# PowerSupply.net
KiCad netlist of a schematic drawn in Altium Designer
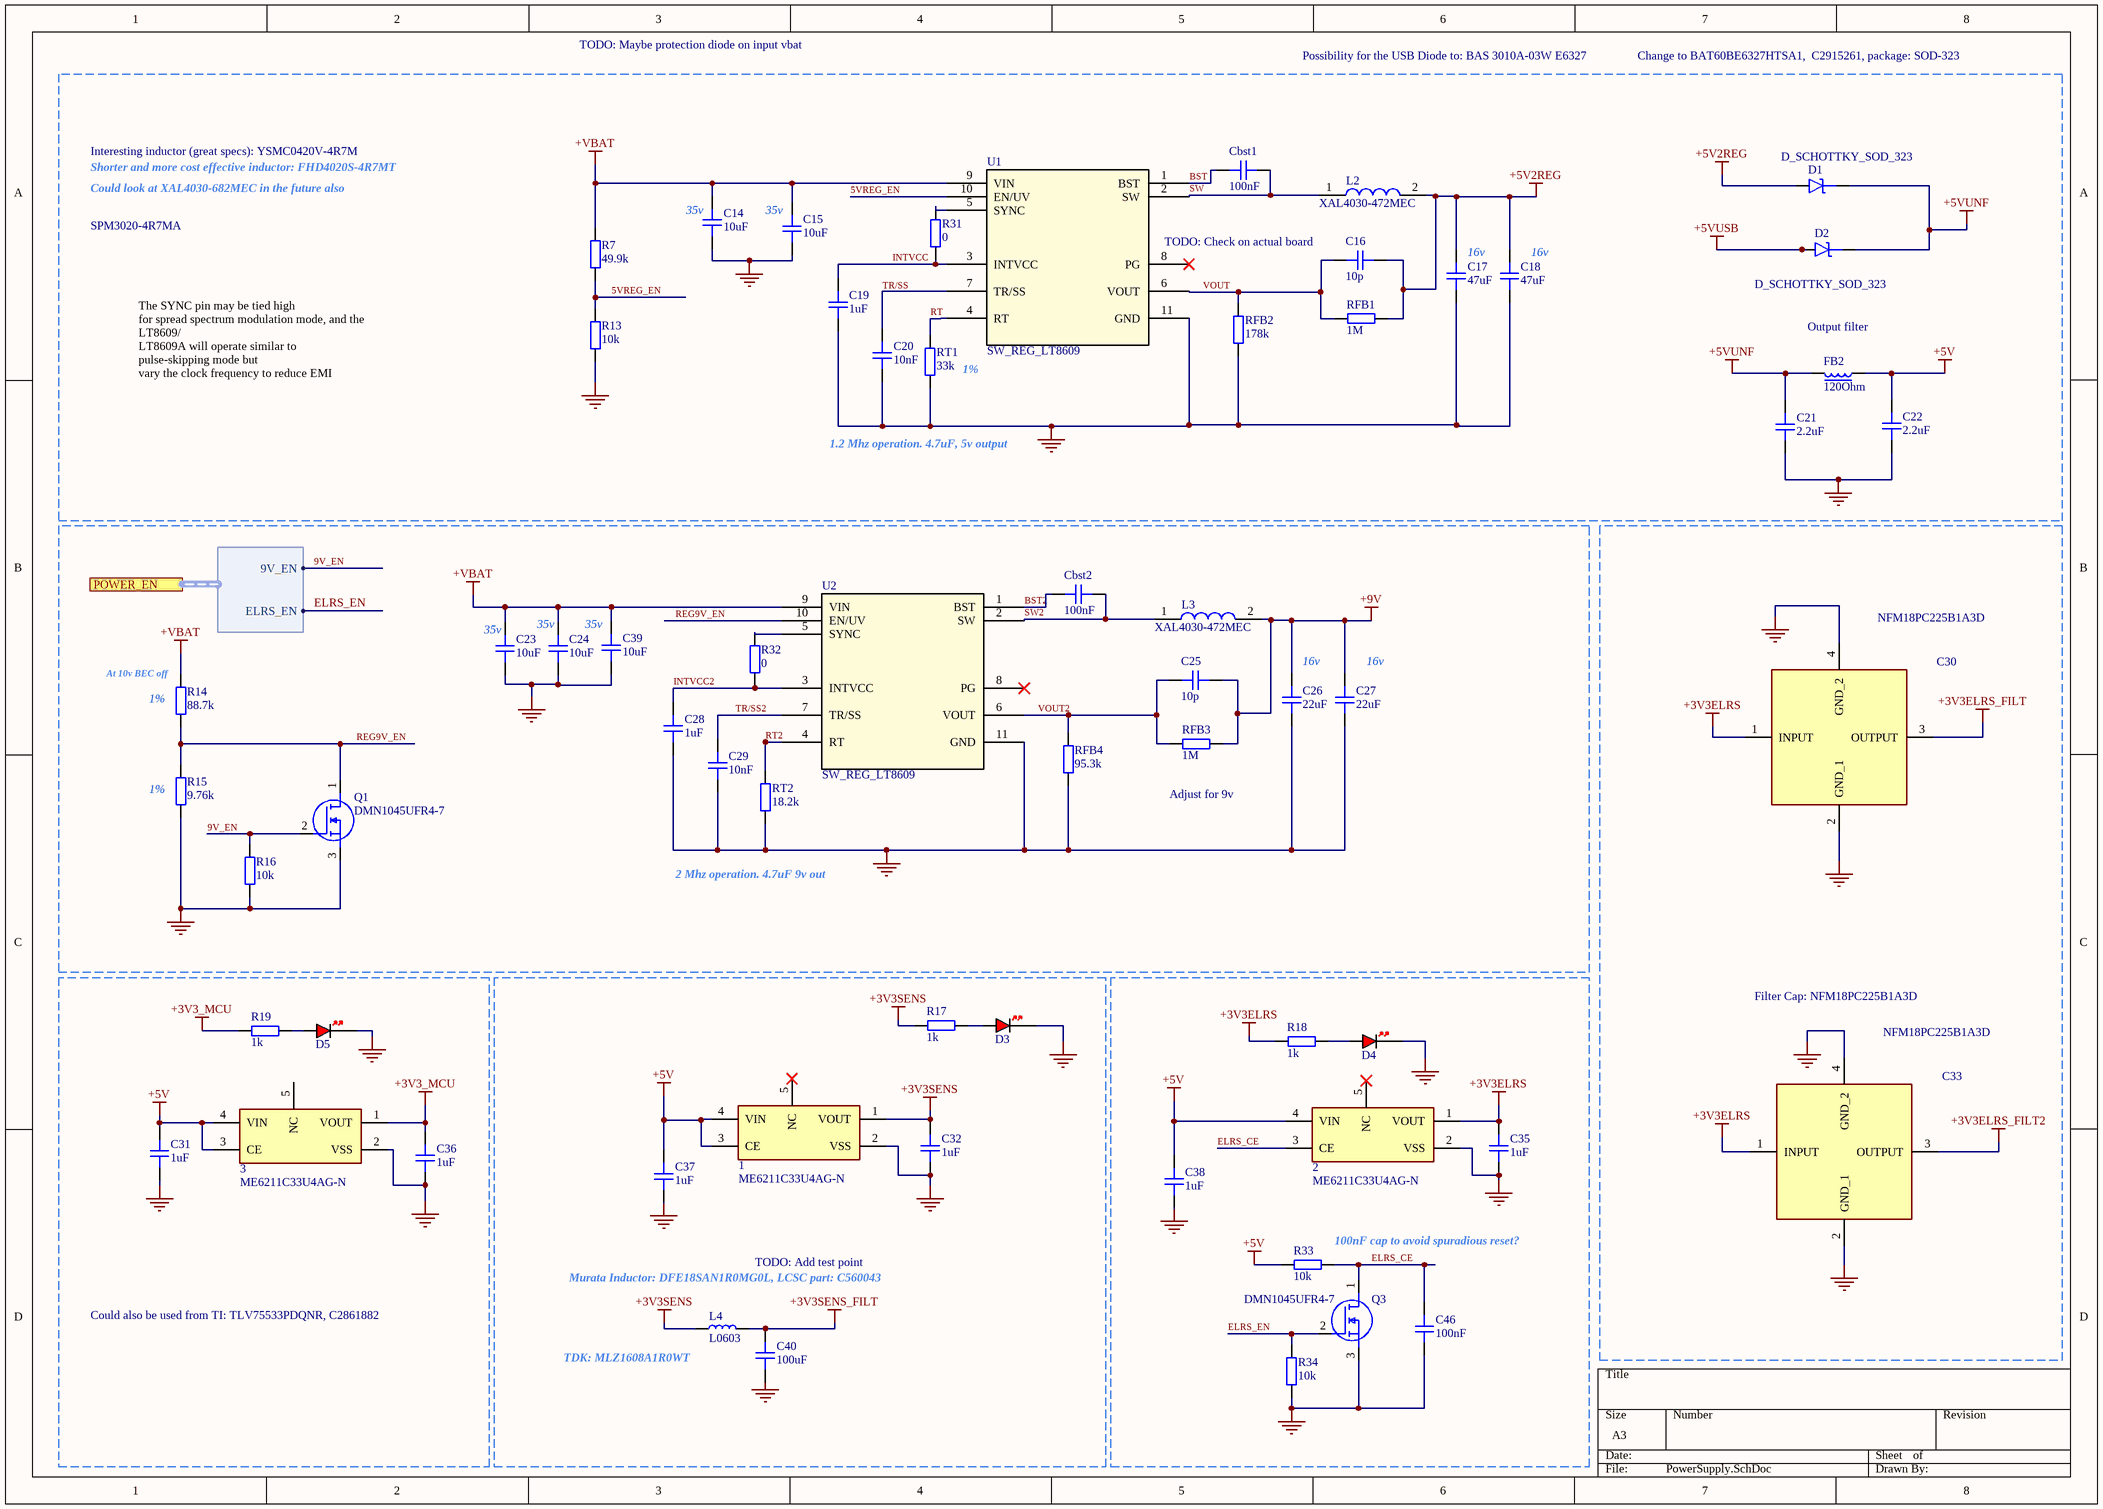
[diagram p0: PowerSupply.SchDoc]

(export (version "E")
  (design (tool "Eeschema 10.0.6"))
  (components
    (comp (ref "1")
      (value "ME6211C33U4AG-N")
      (footprint "Footprint-Lib-Singu:X2-SON-4-EP(1x1)")
      (description "Integrated Circuit")
      (fields
        (field (name "MANUFACTURER_PART_NUMBER") "ME6211C33M5G-N")
        (field (name "LCSC PART #") "C82942")
      )
      (libsource (lib "Schematic-Lib-Singu") (part "ME6211C33U4AG-N"))
    )
    (comp (ref "2")
      (value "ME6211C33U4AG-N")
      (footprint "Footprint-Lib-Singu:X2-SON-4-EP(1x1)")
      (description "Integrated Circuit")
      (fields
        (field (name "MANUFACTURER_PART_NUMBER") "ME6211C33M5G-N")
        (field (name "LCSC PART #") "C82942")
      )
      (libsource (lib "Schematic-Lib-Singu") (part "ME6211C33U4AG-N"))
    )
    (comp (ref "3")
      (value "ME6211C33U4AG-N")
      (footprint "Footprint-Lib-Singu:X2-SON-4-EP(1x1)")
      (description "Integrated Circuit")
      (fields
        (field (name "MANUFACTURER_PART_NUMBER") "ME6211C33M5G-N")
        (field (name "LCSC PART #") "C82942")
      )
      (libsource (lib "Schematic-Lib-Singu") (part "ME6211C33U4AG-N"))
    )
    (comp (ref "C14")
      (value "10uF")
      (footprint "CAP_0805")
      (description "Capacitor SMD 0805")
      (libsource (lib "Schematic-Lib-PhilsLab") (part "CAP_0805"))
    )
    (comp (ref "C15")
      (value "10uF")
      (footprint "CAP_0805")
      (description "Capacitor SMD 0805")
      (libsource (lib "Schematic-Lib-PhilsLab") (part "CAP_0805"))
    )
    (comp (ref "C16")
      (value "10p")
      (footprint "CAP_0201")
      (description "Capacitor SMD 0201")
      (libsource (lib "Schematic-Lib-PhilsLab") (part "CAP_0201"))
    )
    (comp (ref "C17")
      (value "47uF")
      (footprint "CAP_0603")
      (description "Capacitor SMD 0603")
      (libsource (lib "Schematic-Lib-PhilsLab") (part "CAP_0603"))
    )
    (comp (ref "C18")
      (value "47uF")
      (footprint "CAP_0603")
      (description "Capacitor SMD 0603")
      (libsource (lib "Schematic-Lib-PhilsLab") (part "CAP_0603"))
    )
    (comp (ref "C19")
      (value "1uF")
      (footprint "CAP_0402")
      (description "Capacitor SMD 0402")
      (libsource (lib "Schematic-Lib-PhilsLab") (part "CAP_0402"))
    )
    (comp (ref "C20")
      (value "10nF")
      (footprint "CAP_0201")
      (description "Capacitor SMD 0201")
      (libsource (lib "Schematic-Lib-PhilsLab") (part "CAP_0201"))
    )
    (comp (ref "C21")
      (value "2.2uF")
      (footprint "CAP_0402")
      (description "Capacitor SMD 0402")
      (libsource (lib "Schematic-Lib-PhilsLab") (part "CAP_0402"))
    )
    (comp (ref "C22")
      (value "2.2uF")
      (footprint "CAP_0402")
      (description "Capacitor SMD 0402")
      (libsource (lib "Schematic-Lib-PhilsLab") (part "CAP_0402"))
    )
    (comp (ref "C23")
      (value "10uF")
      (footprint "CAP_0805")
      (description "Capacitor SMD 0805")
      (libsource (lib "Schematic-Lib-PhilsLab") (part "CAP_0805"))
    )
    (comp (ref "C24")
      (value "10uF")
      (footprint "CAP_0805")
      (description "Capacitor SMD 0805")
      (libsource (lib "Schematic-Lib-PhilsLab") (part "CAP_0805"))
    )
    (comp (ref "C25")
      (value "10p")
      (footprint "CAP_0201")
      (description "Capacitor SMD 0201")
      (libsource (lib "Schematic-Lib-PhilsLab") (part "CAP_0201"))
    )
    (comp (ref "C26")
      (value "22uF")
      (footprint "CAP_0603")
      (description "Capacitor SMD 0603")
      (libsource (lib "Schematic-Lib-PhilsLab") (part "CAP_0603"))
    )
    (comp (ref "C27")
      (value "22uF")
      (footprint "CAP_0603")
      (description "Capacitor SMD 0603")
      (libsource (lib "Schematic-Lib-PhilsLab") (part "CAP_0603"))
    )
    (comp (ref "C28")
      (value "1uF")
      (footprint "CAP_0402")
      (description "Capacitor SMD 0402")
      (libsource (lib "Schematic-Lib-PhilsLab") (part "CAP_0402"))
    )
    (comp (ref "C29")
      (value "10nF")
      (footprint "CAP_0201")
      (description "Capacitor SMD 0201")
      (libsource (lib "Schematic-Lib-PhilsLab") (part "CAP_0201"))
    )
    (comp (ref "C30")
      (value "NFM18PC225B1A3D")
      (footprint "SamacSys:NFM18PC225B1A3D")
      (description "Capacitor")
      (fields (field (name "MOUSER PART NUMBER") "81-NFM18PC225B1A3D"))
      (libsource (lib "*") (part "NFM18PC225B1A3D"))
    )
    (comp (ref "C31")
      (value "1uF")
      (footprint "CAP_0402")
      (description "Capacitor SMD 0402")
      (libsource (lib "Schematic-Lib-PhilsLab") (part "CAP_0402"))
    )
    (comp (ref "C32")
      (value "1uF")
      (footprint "CAP_0402")
      (description "Capacitor SMD 0402")
      (libsource (lib "Schematic-Lib-PhilsLab") (part "CAP_0402"))
    )
    (comp (ref "C33")
      (value "NFM18PC225B1A3D")
      (footprint "SamacSys:NFM18PC225B1A3D")
      (description "Capacitor")
      (fields (field (name "MOUSER PART NUMBER") "81-NFM18PC225B1A3D"))
      (libsource (lib "*") (part "NFM18PC225B1A3D"))
    )
    (comp (ref "C35")
      (value "1uF")
      (footprint "CAP_0402")
      (description "Capacitor SMD 0402")
      (libsource (lib "Schematic-Lib-PhilsLab") (part "CAP_0402"))
    )
    (comp (ref "C36")
      (value "1uF")
      (footprint "CAP_0402")
      (description "Capacitor SMD 0402")
      (libsource (lib "Schematic-Lib-PhilsLab") (part "CAP_0402"))
    )
    (comp (ref "C37")
      (value "1uF")
      (footprint "CAP_0402")
      (description "Capacitor SMD 0402")
      (libsource (lib "Schematic-Lib-PhilsLab") (part "CAP_0402"))
    )
    (comp (ref "C38")
      (value "1uF")
      (footprint "CAP_0402")
      (description "Capacitor SMD 0402")
      (libsource (lib "Schematic-Lib-PhilsLab") (part "CAP_0402"))
    )
    (comp (ref "C39")
      (value "10uF")
      (footprint "CAP_0603")
      (description "Capacitor SMD 0603")
      (libsource (lib "Schematic-Lib-PhilsLab") (part "CAP_0603"))
    )
    (comp (ref "C40")
      (value "100uF")
      (footprint "CAP_0805")
      (description "Capacitor SMD 0805")
      (libsource (lib "Schematic-Lib-PhilsLab") (part "CAP_0805"))
    )
    (comp (ref "C46")
      (value "100nF")
      (footprint "CAP_0201")
      (description "Capacitor SMD 0201")
      (libsource (lib "Schematic-Lib-PhilsLab") (part "CAP_0201"))
    )
    (comp (ref "Cbst1")
      (value "100nF")
      (footprint "CAP_0201")
      (description "Capacitor SMD 0201")
      (libsource (lib "Schematic-Lib-PhilsLab") (part "CAP_0201"))
    )
    (comp (ref "Cbst2")
      (value "100nF")
      (footprint "CAP_0201")
      (description "Capacitor SMD 0201")
      (libsource (lib "Schematic-Lib-PhilsLab") (part "CAP_0201"))
    )
    (comp (ref "D1")
      (value "D_SCHOTTKY_SOD_323")
      (footprint "SOD-323")
      (description "Diode Schottky SMD SOD-323")
      (libsource (lib "Schematic-Lib-PhilsLab") (part "D_SCHOTTKY_SOD_323"))
    )
    (comp (ref "D2")
      (value "D_SCHOTTKY_SOD_323")
      (footprint "SOD-323")
      (description "Diode Schottky SMD SOD-323")
      (libsource (lib "Schematic-Lib-PhilsLab") (part "D_SCHOTTKY_SOD_323"))
    )
    (comp (ref "D3")
      (value "RED")
      (footprint "LED_0402_RED")
      (description "LED 0402 RED SMD")
      (libsource (lib "Schematic-Lib-PhilsLab") (part "LED_0402_RED"))
    )
    (comp (ref "D4")
      (value "RED")
      (footprint "LED_0402_RED")
      (description "LED 0402 RED SMD")
      (libsource (lib "Schematic-Lib-PhilsLab") (part "LED_0402_RED"))
    )
    (comp (ref "D5")
      (value "RED")
      (footprint "LED_0402_RED")
      (description "LED 0402 RED SMD")
      (libsource (lib "Schematic-Lib-PhilsLab") (part "LED_0402_RED"))
    )
    (comp (ref "FB2")
      (value "120Ohm")
      (footprint "FB_0603")
      (description "Ferrite Bead SMD 0603")
      (libsource (lib "Schematic-Lib-PhilsLab") (part "FB_0603"))
    )
    (comp (ref "L2")
      (value "XAL4030-472MEC")
      (footprint "Footprint-Lib-Singu:IND-SMD_L4.0-W4.0")
      (description "Inductor")
      (fields (field (name "MOUSER PART NUMBER") "994-XAL4030-472MEC"))
      (libsource (lib "Schematic-Lib-Singu") (part "XAL4030-472MEC"))
    )
    (comp (ref "L3")
      (value "XAL4030-472MEC")
      (footprint "Footprint-Lib-Singu:IND-SMD_L4.0-W4.0")
      (description "Inductor")
      (fields (field (name "MOUSER PART NUMBER") "994-XAL4030-472MEC"))
      (libsource (lib "Schematic-Lib-Singu") (part "XAL4030-472MEC"))
    )
    (comp (ref "L4")
      (value "L0603")
      (footprint "IND_0603")
      (description "Inductor SMD 0603")
      (libsource (lib "Schematic-Lib-PhilsLab") (part "IND_0603"))
    )
    (comp (ref "Q1")
      (value "DMN1045UFR4-7")
      (footprint "Footprint-Lib-Singu:DMP1200UFR47")
      (description "MOSFET (N-Channel)")
      (fields (field (name "MOUSER PART NUMBER") "621-DMN1045UFR4-7"))
      (libsource (lib "Schematic-Lib-Singu") (part "DMN1045UFR4-7"))
    )
    (comp (ref "Q3")
      (value "DMN1045UFR4-7")
      (footprint "Footprint-Lib-Singu:DMP1200UFR47")
      (description "MOSFET (N-Channel)")
      (fields (field (name "MOUSER PART NUMBER") "621-DMN1045UFR4-7"))
      (libsource (lib "Schematic-Lib-Singu") (part "DMN1045UFR4-7"))
    )
    (comp (ref "R7")
      (value "49.9k")
      (footprint "RES_0402")
      (description "Resistor SMD 0402")
      (libsource (lib "Schematic-Lib-PhilsLab") (part "RES_0402"))
    )
    (comp (ref "R13")
      (value "10k")
      (footprint "RES_0201")
      (description "Resistor SMD 0201")
      (libsource (lib "Schematic-Lib-PhilsLab") (part "RES_0201"))
    )
    (comp (ref "R14")
      (value "88.7k")
      (footprint "RES_0402")
      (description "Resistor SMD 0402")
      (libsource (lib "Schematic-Lib-PhilsLab") (part "RES_0402"))
    )
    (comp (ref "R15")
      (value "9.76k")
      (footprint "RES_0201")
      (description "Resistor SMD 0201")
      (libsource (lib "Schematic-Lib-PhilsLab") (part "RES_0201"))
    )
    (comp (ref "R16")
      (value "10k")
      (footprint "RES_0201")
      (description "Resistor SMD 0201")
      (libsource (lib "Schematic-Lib-PhilsLab") (part "RES_0201"))
    )
    (comp (ref "R17")
      (value "1k")
      (footprint "RES_0201")
      (description "Resistor SMD 0201")
      (libsource (lib "Schematic-Lib-PhilsLab") (part "RES_0201"))
    )
    (comp (ref "R18")
      (value "1k")
      (footprint "RES_0201")
      (description "Resistor SMD 0201")
      (libsource (lib "Schematic-Lib-PhilsLab") (part "RES_0201"))
    )
    (comp (ref "R19")
      (value "1k")
      (footprint "RES_0201")
      (description "Resistor SMD 0201")
      (libsource (lib "Schematic-Lib-PhilsLab") (part "RES_0201"))
    )
    (comp (ref "R31")
      (value "0")
      (footprint "RES_0201")
      (description "Resistor SMD 0201")
      (libsource (lib "Schematic-Lib-PhilsLab") (part "RES_0201"))
    )
    (comp (ref "R32")
      (value "0")
      (footprint "RES_0201")
      (description "Resistor SMD 0201")
      (libsource (lib "Schematic-Lib-PhilsLab") (part "RES_0201"))
    )
    (comp (ref "R33")
      (value "10k")
      (footprint "RES_0201")
      (description "Resistor SMD 0201")
      (libsource (lib "Schematic-Lib-PhilsLab") (part "RES_0201"))
    )
    (comp (ref "R34")
      (value "10k")
      (footprint "RES_0201")
      (description "Resistor SMD 0201")
      (libsource (lib "Schematic-Lib-PhilsLab") (part "RES_0201"))
    )
    (comp (ref "RFB1")
      (value "1M")
      (footprint "RES_0201")
      (description "Resistor SMD 0201")
      (libsource (lib "Schematic-Lib-PhilsLab") (part "RES_0201"))
    )
    (comp (ref "RFB2")
      (value "178k")
      (footprint "RES_0201")
      (description "Resistor SMD 0201")
      (libsource (lib "Schematic-Lib-PhilsLab") (part "RES_0201"))
    )
    (comp (ref "RFB3")
      (value "1M")
      (footprint "RES_0201")
      (description "Resistor SMD 0201")
      (libsource (lib "Schematic-Lib-PhilsLab") (part "RES_0201"))
    )
    (comp (ref "RFB4")
      (value "95.3k")
      (footprint "RES_0201")
      (description "Resistor SMD 0201")
      (libsource (lib "Schematic-Lib-PhilsLab") (part "RES_0201"))
    )
    (comp (ref "RT1")
      (value "33k")
      (footprint "RES_0201")
      (description "Resistor SMD 0201")
      (libsource (lib "Schematic-Lib-PhilsLab") (part "RES_0201"))
    )
    (comp (ref "RT2")
      (value "18.2k")
      (footprint "RES_0201")
      (description "Resistor SMD 0201")
      (libsource (lib "Schematic-Lib-PhilsLab") (part "RES_0201"))
    )
    (comp (ref "U1")
      (value "SW_REG_LT8609")
      (footprint "SW_REG_LT8609")
      (fields (field (name "MFR.PART") "LT8609AJDDM#WTRPBF") (field (name "LCSC PART #") "C5122347"))
      (libsource (lib "Schematic-Lib-Singu") (part "SW_REG_LT8609"))
    )
    (comp (ref "U2")
      (value "SW_REG_LT8609")
      (footprint "SW_REG_LT8609")
      (fields (field (name "MFR.PART") "LT8609AJDDM#WTRPBF") (field (name "LCSC PART #") "C5122347"))
      (libsource (lib "Schematic-Lib-Singu") (part "SW_REG_LT8609"))
    )
  )
  (nets
    (net (code "2") (name "+3V3ELRS") (class "Default")
      (node (ref "2") (pin "1") (pinfunction "VOUT_1") (pintype "passive"))
      (node (ref "C30") (pin "1") (pinfunction "INPUT_1") (pintype "passive"))
      (node (ref "C33") (pin "1") (pinfunction "INPUT_1") (pintype "passive"))
      (node (ref "C35") (pin "2") (pinfunction "2_2") (pintype "passive"))
      (node (ref "R18") (pin "1") (pinfunction "1_1") (pintype "passive"))
    )
    (net (code "3") (name "+3V3ELRS_FILT") (class "Default")
      (node (ref "C30") (pin "3") (pinfunction "OUTPUT_3") (pintype "passive"))
    )
    (net (code "4") (name "+3V3ELRS_FILT2") (class "Default")
      (node (ref "C33") (pin "3") (pinfunction "OUTPUT_3") (pintype "passive"))
    )
    (net (code "5") (name "+3V3SENS") (class "Default")
      (node (ref "1") (pin "1") (pinfunction "VOUT_1") (pintype "passive"))
      (node (ref "C32") (pin "2") (pinfunction "2_2") (pintype "passive"))
      (node (ref "L4") (pin "1") (pinfunction "1_1") (pintype "passive"))
      (node (ref "R17") (pin "1") (pinfunction "1_1") (pintype "passive"))
    )
    (net (code "6") (name "+3V3SENS_FILT") (class "Default")
      (node (ref "C40") (pin "2") (pinfunction "2_2") (pintype "passive"))
      (node (ref "L4") (pin "2") (pinfunction "2_2") (pintype "passive"))
    )
    (net (code "7") (name "+3V3_MCU") (class "Default")
      (node (ref "3") (pin "1") (pinfunction "VOUT_1") (pintype "passive"))
      (node (ref "C36") (pin "2") (pinfunction "2_2") (pintype "passive"))
      (node (ref "R19") (pin "1") (pinfunction "1_1") (pintype "passive"))
    )
    (net (code "8") (name "+5V") (class "Default")
      (node (ref "1") (pin "3") (pinfunction "CE_3") (pintype "passive"))
      (node (ref "1") (pin "4") (pinfunction "VIN_4") (pintype "passive"))
      (node (ref "2") (pin "4") (pinfunction "VIN_4") (pintype "passive"))
      (node (ref "3") (pin "3") (pinfunction "CE_3") (pintype "passive"))
      (node (ref "3") (pin "4") (pinfunction "VIN_4") (pintype "passive"))
      (node (ref "C22") (pin "2") (pinfunction "2_2") (pintype "passive"))
      (node (ref "C31") (pin "2") (pinfunction "2_2") (pintype "passive"))
      (node (ref "C37") (pin "2") (pinfunction "2_2") (pintype "passive"))
      (node (ref "C38") (pin "2") (pinfunction "2_2") (pintype "passive"))
      (node (ref "FB2") (pin "1") (pinfunction "1_1") (pintype "passive"))
      (node (ref "R33") (pin "2") (pinfunction "2_2") (pintype "passive"))
    )
    (net (code "9") (name "+5V2REG") (class "Default")
      (node (ref "C16") (pin "2") (pinfunction "2_2") (pintype "passive"))
      (node (ref "C17") (pin "1") (pinfunction "1_1") (pintype "passive"))
      (node (ref "C18") (pin "1") (pinfunction "1_1") (pintype "passive"))
      (node (ref "D1") (pin "A") (pinfunction "A_A") (pintype "passive"))
      (node (ref "L2") (pin "2") (pinfunction "2_2") (pintype "passive"))
      (node (ref "RFB1") (pin "1") (pinfunction "1_1") (pintype "passive"))
    )
    (net (code "10") (name "+5VUNF") (class "Default")
      (node (ref "C21") (pin "2") (pinfunction "2_2") (pintype "passive"))
      (node (ref "D1") (pin "K") (pinfunction "K_K") (pintype "passive"))
      (node (ref "D2") (pin "K") (pinfunction "K_K") (pintype "passive"))
      (node (ref "FB2") (pin "2") (pinfunction "2_2") (pintype "passive"))
    )
    (net (code "11") (name "+5VUSB") (class "Default")
      (node (ref "D2") (pin "A") (pinfunction "A_A") (pintype "passive"))
    )
    (net (code "12") (name "+9V") (class "Default")
      (node (ref "C25") (pin "2") (pinfunction "2_2") (pintype "passive"))
      (node (ref "C26") (pin "1") (pinfunction "1_1") (pintype "passive"))
      (node (ref "C27") (pin "1") (pinfunction "1_1") (pintype "passive"))
      (node (ref "L3") (pin "2") (pinfunction "2_2") (pintype "passive"))
      (node (ref "RFB3") (pin "1") (pinfunction "1_1") (pintype "passive"))
    )
    (net (code "13") (name "+VBAT") (class "Default")
      (node (ref "C14") (pin "2") (pinfunction "2_2") (pintype "passive"))
      (node (ref "C15") (pin "2") (pinfunction "2_2") (pintype "passive"))
      (node (ref "C23") (pin "2") (pinfunction "2_2") (pintype "passive"))
      (node (ref "C24") (pin "2") (pinfunction "2_2") (pintype "passive"))
      (node (ref "C39") (pin "2") (pinfunction "2_2") (pintype "passive"))
      (node (ref "R14") (pin "2") (pinfunction "2_2") (pintype "passive"))
      (node (ref "R7") (pin "2") (pinfunction "2_2") (pintype "passive"))
      (node (ref "U1") (pin "9") (pinfunction "VIN_9") (pintype "passive"))
      (node (ref "U2") (pin "9") (pinfunction "VIN_9") (pintype "passive"))
    )
    (net (code "14") (name "/5VREG_EN") (class "Default")
      (node (ref "R13") (pin "2") (pinfunction "2_2") (pintype "passive"))
      (node (ref "R7") (pin "1") (pinfunction "1_1") (pintype "passive"))
      (node (ref "U1") (pin "10") (pinfunction "EN/UV_10") (pintype "passive"))
    )
    (net (code "15") (name "/9V_EN") (class "Default")
      (node (ref "Q1") (pin "2") (pinfunction "G_2") (pintype "passive"))
      (node (ref "R16") (pin "2") (pinfunction "2_2") (pintype "passive"))
    )
    (net (code "16") (name "/BST") (class "Default")
      (node (ref "Cbst1") (pin "1") (pinfunction "1_1") (pintype "passive"))
      (node (ref "U1") (pin "1") (pinfunction "BST_1") (pintype "passive"))
    )
    (net (code "17") (name "/BST2") (class "Default")
      (node (ref "Cbst2") (pin "1") (pinfunction "1_1") (pintype "passive"))
      (node (ref "U2") (pin "1") (pinfunction "BST_1") (pintype "passive"))
    )
    (net (code "18") (name "/ELRS_CE") (class "Default")
      (node (ref "2") (pin "3") (pinfunction "CE_3") (pintype "passive"))
      (node (ref "C46") (pin "2") (pinfunction "2_2") (pintype "passive"))
      (node (ref "Q3") (pin "1") (pinfunction "D_1") (pintype "passive"))
      (node (ref "R33") (pin "1") (pinfunction "1_1") (pintype "passive"))
    )
    (net (code "19") (name "/ELRS_EN") (class "Default")
      (node (ref "Q3") (pin "2") (pinfunction "G_2") (pintype "passive"))
      (node (ref "R34") (pin "2") (pinfunction "2_2") (pintype "passive"))
    )
    (net (code "20") (name "/INTVCC") (class "Default")
      (node (ref "C19") (pin "2") (pinfunction "2_2") (pintype "passive"))
      (node (ref "R31") (pin "1") (pinfunction "1_1") (pintype "passive"))
      (node (ref "U1") (pin "3") (pinfunction "INTVCC_3") (pintype "passive"))
    )
    (net (code "21") (name "/INTVCC2") (class "Default")
      (node (ref "C28") (pin "2") (pinfunction "2_2") (pintype "passive"))
      (node (ref "R32") (pin "1") (pinfunction "1_1") (pintype "passive"))
      (node (ref "U2") (pin "3") (pinfunction "INTVCC_3") (pintype "passive"))
    )
    (net (code "22") (name "/REG9V_EN") (class "Default")
      (node (ref "Q1") (pin "1") (pinfunction "D_1") (pintype "passive"))
      (node (ref "R14") (pin "1") (pinfunction "1_1") (pintype "passive"))
      (node (ref "R15") (pin "2") (pinfunction "2_2") (pintype "passive"))
      (node (ref "U2") (pin "10") (pinfunction "EN/UV_10") (pintype "passive"))
    )
    (net (code "23") (name "/RT") (class "Default")
      (node (ref "RT1") (pin "2") (pinfunction "2_2") (pintype "passive"))
      (node (ref "U1") (pin "4") (pinfunction "RT_4") (pintype "passive"))
    )
    (net (code "24") (name "/RT2") (class "Default")
      (node (ref "RT2") (pin "1") (pinfunction "1_1") (pintype "passive"))
      (node (ref "U2") (pin "4") (pinfunction "RT_4") (pintype "passive"))
    )
    (net (code "25") (name "/SW") (class "Default")
      (node (ref "Cbst1") (pin "2") (pinfunction "2_2") (pintype "passive"))
      (node (ref "L2") (pin "1") (pinfunction "1_1") (pintype "passive"))
      (node (ref "U1") (pin "2") (pinfunction "SW_2") (pintype "passive"))
    )
    (net (code "26") (name "/SW2") (class "Default")
      (node (ref "Cbst2") (pin "2") (pinfunction "2_2") (pintype "passive"))
      (node (ref "L3") (pin "1") (pinfunction "1_1") (pintype "passive"))
      (node (ref "U2") (pin "2") (pinfunction "SW_2") (pintype "passive"))
    )
    (net (code "27") (name "/TR{slash}SS") (class "Default")
      (node (ref "C20") (pin "2") (pinfunction "2_2") (pintype "passive"))
      (node (ref "U1") (pin "7") (pinfunction "TR/SS_7") (pintype "passive"))
    )
    (net (code "28") (name "/TR{slash}SS2") (class "Default")
      (node (ref "C29") (pin "2") (pinfunction "2_2") (pintype "passive"))
      (node (ref "U2") (pin "7") (pinfunction "TR/SS_7") (pintype "passive"))
    )
    (net (code "29") (name "/VOUT") (class "Default")
      (node (ref "C16") (pin "1") (pinfunction "1_1") (pintype "passive"))
      (node (ref "RFB1") (pin "2") (pinfunction "2_2") (pintype "passive"))
      (node (ref "RFB2") (pin "2") (pinfunction "2_2") (pintype "passive"))
      (node (ref "U1") (pin "6") (pinfunction "VOUT_6") (pintype "passive"))
    )
    (net (code "30") (name "/VOUT2") (class "Default")
      (node (ref "C25") (pin "1") (pinfunction "1_1") (pintype "passive"))
      (node (ref "RFB3") (pin "2") (pinfunction "2_2") (pintype "passive"))
      (node (ref "RFB4") (pin "2") (pinfunction "2_2") (pintype "passive"))
      (node (ref "U2") (pin "6") (pinfunction "VOUT_6") (pintype "passive"))
    )
    (net (code "32") (name "GND") (class "Default")
      (node (ref "1") (pin "2") (pinfunction "VSS_2") (pintype "passive"))
      (node (ref "2") (pin "2") (pinfunction "VSS_2") (pintype "passive"))
      (node (ref "3") (pin "2") (pinfunction "VSS_2") (pintype "passive"))
      (node (ref "C14") (pin "1") (pinfunction "1_1") (pintype "passive"))
      (node (ref "C15") (pin "1") (pinfunction "1_1") (pintype "passive"))
      (node (ref "C17") (pin "2") (pinfunction "2_2") (pintype "passive"))
      (node (ref "C18") (pin "2") (pinfunction "2_2") (pintype "passive"))
      (node (ref "C19") (pin "1") (pinfunction "1_1") (pintype "passive"))
      (node (ref "C20") (pin "1") (pinfunction "1_1") (pintype "passive"))
      (node (ref "C21") (pin "1") (pinfunction "1_1") (pintype "passive"))
      (node (ref "C22") (pin "1") (pinfunction "1_1") (pintype "passive"))
      (node (ref "C23") (pin "1") (pinfunction "1_1") (pintype "passive"))
      (node (ref "C24") (pin "1") (pinfunction "1_1") (pintype "passive"))
      (node (ref "C26") (pin "2") (pinfunction "2_2") (pintype "passive"))
      (node (ref "C27") (pin "2") (pinfunction "2_2") (pintype "passive"))
      (node (ref "C28") (pin "1") (pinfunction "1_1") (pintype "passive"))
      (node (ref "C29") (pin "1") (pinfunction "1_1") (pintype "passive"))
      (node (ref "C30") (pin "2") (pinfunction "GND_1_2") (pintype "passive"))
      (node (ref "C30") (pin "4") (pinfunction "GND_2_4") (pintype "passive"))
      (node (ref "C31") (pin "1") (pinfunction "1_1") (pintype "passive"))
      (node (ref "C32") (pin "1") (pinfunction "1_1") (pintype "passive"))
      (node (ref "C33") (pin "2") (pinfunction "GND_1_2") (pintype "passive"))
      (node (ref "C33") (pin "4") (pinfunction "GND_2_4") (pintype "passive"))
      (node (ref "C35") (pin "1") (pinfunction "1_1") (pintype "passive"))
      (node (ref "C36") (pin "1") (pinfunction "1_1") (pintype "passive"))
      (node (ref "C37") (pin "1") (pinfunction "1_1") (pintype "passive"))
      (node (ref "C38") (pin "1") (pinfunction "1_1") (pintype "passive"))
      (node (ref "C39") (pin "1") (pinfunction "1_1") (pintype "passive"))
      (node (ref "C40") (pin "1") (pinfunction "1_1") (pintype "passive"))
      (node (ref "C46") (pin "1") (pinfunction "1_1") (pintype "passive"))
      (node (ref "D3") (pin "K") (pinfunction "K_K") (pintype "passive"))
      (node (ref "D4") (pin "K") (pinfunction "K_K") (pintype "passive"))
      (node (ref "D5") (pin "K") (pinfunction "K_K") (pintype "passive"))
      (node (ref "Q1") (pin "3") (pinfunction "S_3") (pintype "passive"))
      (node (ref "Q3") (pin "3") (pinfunction "S_3") (pintype "passive"))
      (node (ref "R13") (pin "1") (pinfunction "1_1") (pintype "passive"))
      (node (ref "R15") (pin "1") (pinfunction "1_1") (pintype "passive"))
      (node (ref "R16") (pin "1") (pinfunction "1_1") (pintype "passive"))
      (node (ref "R34") (pin "1") (pinfunction "1_1") (pintype "passive"))
      (node (ref "RFB2") (pin "1") (pinfunction "1_1") (pintype "passive"))
      (node (ref "RFB4") (pin "1") (pinfunction "1_1") (pintype "passive"))
      (node (ref "RT1") (pin "1") (pinfunction "1_1") (pintype "passive"))
      (node (ref "RT2") (pin "2") (pinfunction "2_2") (pintype "passive"))
      (node (ref "U1") (pin "11") (pinfunction "GND_11") (pintype "passive"))
      (node (ref "U2") (pin "11") (pinfunction "GND_11") (pintype "passive"))
    )
    (net (code "33") (name "Net-(D3-PadA)") (class "Default")
      (node (ref "D3") (pin "A") (pinfunction "A_A") (pintype "passive"))
      (node (ref "R17") (pin "2") (pinfunction "2_2") (pintype "passive"))
    )
    (net (code "34") (name "Net-(D4-PadA)") (class "Default")
      (node (ref "D4") (pin "A") (pinfunction "A_A") (pintype "passive"))
      (node (ref "R18") (pin "2") (pinfunction "2_2") (pintype "passive"))
    )
    (net (code "35") (name "Net-(D5-PadA)") (class "Default")
      (node (ref "D5") (pin "A") (pinfunction "A_A") (pintype "passive"))
      (node (ref "R19") (pin "2") (pinfunction "2_2") (pintype "passive"))
    )
    (net (code "36") (name "Net-(U1-SYNC)") (class "Default")
      (node (ref "R31") (pin "2") (pinfunction "2_2") (pintype "passive"))
      (node (ref "U1") (pin "5") (pinfunction "SYNC_5") (pintype "passive"))
    )
    (net (code "37") (name "Net-(U2-SYNC)") (class "Default")
      (node (ref "R32") (pin "2") (pinfunction "2_2") (pintype "passive"))
      (node (ref "U2") (pin "5") (pinfunction "SYNC_5") (pintype "passive"))
    )
    (net (code "38") (name "unconnected-(1-NC-Pad5)") (class "Default")
      (node (ref "1") (pin "5") (pinfunction "NC_5") (pintype "passive+no_connect"))
    )
    (net (code "39") (name "unconnected-(2-NC-Pad5)") (class "Default")
      (node (ref "2") (pin "5") (pinfunction "NC_5") (pintype "passive+no_connect"))
    )
    (net (code "40") (name "unconnected-(3-NC-Pad5)") (class "Default")
      (node (ref "3") (pin "5") (pinfunction "NC_5") (pintype "passive"))
    )
    (net (code "41") (name "unconnected-(U1-PG-Pad8)") (class "Default")
      (node (ref "U1") (pin "8") (pinfunction "PG_8") (pintype "passive+no_connect"))
    )
    (net (code "42") (name "unconnected-(U2-PG-Pad8)") (class "Default")
      (node (ref "U2") (pin "8") (pinfunction "PG_8") (pintype "passive+no_connect"))
    )
  )
)
